# motor-driver.net
KiCad netlist of a schematic drawn in Altium Designer
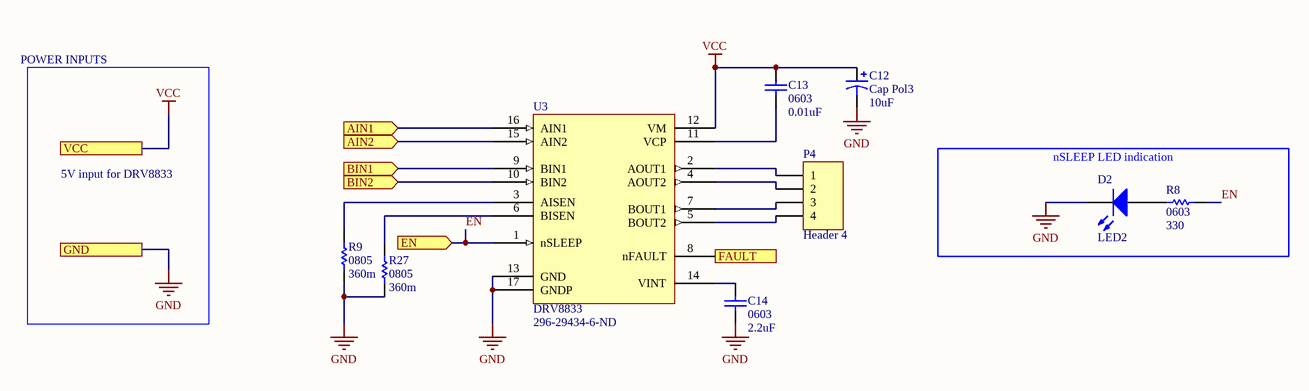
[diagram p0: motor-driver.SchDoc]

(export (version "E")
  (design (tool "Eeschema 10.0.6"))
  (components
    (comp (ref "C12")
      (value "Cap Pol3")
      (footprint "CAP DIA12.5mm")
      (description "Polarized Capacitor (through hole)")
      (fields (field (name "ALTIUM_VALUE") "10uF") (field (name "PUBLISHER") "Altium Limited"))
      (libsource (lib "Miscellaneous Devices") (part "Cap Pol3"))
    )
    (comp (ref "C13")
      (value "0603")
      (footprint "0603-RES")
      (description "Capacitor")
      (fields (field (name "ALTIUM_VALUE") "0.01uF") (field (name "PUBLISHER") "Altium Limited"))
      (libsource (lib "Miscellaneous Devices") (part "Cap"))
    )
    (comp (ref "C14")
      (value "0603")
      (footprint "0603-RES")
      (description "Capacitor")
      (fields (field (name "ALTIUM_VALUE") "2.2uF") (field (name "PUBLISHER") "Altium Limited"))
      (libsource (lib "Miscellaneous Devices") (part "Cap"))
    )
    (comp (ref "D2")
      (value "LED2")
      (footprint "0603-LED")
      (description "Typical RED, GREEN, YELLOW, AMBER GaAs LED")
      (fields (field (name "PUBLISHER") "Altium Limited"))
      (libsource (lib "Miscellaneous Devices") (part "LED2"))
    )
    (comp (ref "P4")
      (value "Header 4")
      (footprint "MOLEX_504050-0491")
      (description "Header, 4-Pin")
      (fields (field (name "PUBLISHER") "Altium Limited"))
      (libsource (lib "Miscellaneous Connectors") (part "Header 4"))
    )
    (comp (ref "R8")
      (value "0603")
      (footprint "0603-RES")
      (description "Resistor")
      (fields (field (name "ALTIUM_VALUE") "330") (field (name "PUBLISHER") "Altium Limited"))
      (libsource (lib "Miscellaneous Devices") (part "Res1"))
    )
    (comp (ref "R9")
      (value "0805")
      (footprint "6-0805_M")
      (description "Resistor")
      (fields (field (name "ALTIUM_VALUE") "360m") (field (name "PUBLISHER") "Altium Limited"))
      (libsource (lib "Miscellaneous Devices") (part "Res1"))
    )
    (comp (ref "R27")
      (value "0805")
      (footprint "6-0805_M")
      (description "Resistor")
      (fields (field (name "ALTIUM_VALUE") "360m") (field (name "PUBLISHER") "Altium Limited"))
      (libsource (lib "Miscellaneous Devices") (part "Res1"))
    )
    (comp (ref "U3")
      (value "DRV8833")
      (footprint "SOP65P640X120-17N")
      (fields (field (name "SUPPLIER PART NUMBER 1") "296-29434-6-ND"))
      (libsource (lib "PAY") (part "DRV8833"))
    )
  )
  (nets
    (net (code "1") (name "/AIN1") (class "Default")
      (node (ref "U3") (pin "16") (pinfunction "AIN1_16") (pintype "input"))
    )
    (net (code "2") (name "/AIN2") (class "Default")
      (node (ref "U3") (pin "15") (pinfunction "AIN2_15") (pintype "input"))
    )
    (net (code "3") (name "/BIN1") (class "Default")
      (node (ref "U3") (pin "9") (pinfunction "BIN1_9") (pintype "input"))
    )
    (net (code "4") (name "/BIN2") (class "Default")
      (node (ref "U3") (pin "10") (pinfunction "BIN2_10") (pintype "input"))
    )
    (net (code "5") (name "/EN") (class "Default")
      (node (ref "R8") (pin "2") (pinfunction "2_2") (pintype "passive"))
      (node (ref "U3") (pin "1") (pinfunction "nSLEEP_1") (pintype "input"))
    )
    (net (code "6") (name "/FAULT") (class "Default")
      (node (ref "U3") (pin "8") (pinfunction "nFAULT_8") (pintype "passive"))
    )
    (net (code "7") (name "GND") (class "Default")
      (node (ref "C12") (pin "2") (pinfunction "2_2") (pintype "passive"))
      (node (ref "C14") (pin "1") (pinfunction "1_1") (pintype "passive"))
      (node (ref "D2") (pin "2") (pinfunction "K_2") (pintype "passive"))
      (node (ref "R27") (pin "1") (pinfunction "1_1") (pintype "passive"))
      (node (ref "R9") (pin "1") (pinfunction "1_1") (pintype "passive"))
      (node (ref "U3") (pin "13") (pinfunction "GND_13") (pintype "power_in"))
      (node (ref "U3") (pin "17") (pinfunction "GNDP_17") (pintype "power_in"))
    )
    (net (code "8") (name "Net-(D2-A)") (class "Default")
      (node (ref "D2") (pin "1") (pinfunction "A_1") (pintype "passive"))
      (node (ref "R8") (pin "1") (pinfunction "1_1") (pintype "passive"))
    )
    (net (code "9") (name "Net-(U3-AISEN)") (class "Default")
      (node (ref "R9") (pin "2") (pinfunction "2_2") (pintype "passive"))
      (node (ref "U3") (pin "3") (pinfunction "AISEN_3") (pintype "passive"))
    )
    (net (code "10") (name "Net-(U3-AOUT1)") (class "Default")
      (node (ref "P4") (pin "1") (pinfunction "1_1") (pintype "passive"))
      (node (ref "U3") (pin "2") (pinfunction "AOUT1_2") (pintype "output"))
    )
    (net (code "11") (name "Net-(U3-AOUT2)") (class "Default")
      (node (ref "P4") (pin "2") (pinfunction "2_2") (pintype "passive"))
      (node (ref "U3") (pin "4") (pinfunction "AOUT2_4") (pintype "output"))
    )
    (net (code "12") (name "Net-(U3-BISEN)") (class "Default")
      (node (ref "R27") (pin "2") (pinfunction "2_2") (pintype "passive"))
      (node (ref "U3") (pin "6") (pinfunction "BISEN_6") (pintype "passive"))
    )
    (net (code "13") (name "Net-(U3-BOUT1)") (class "Default")
      (node (ref "P4") (pin "3") (pinfunction "3_3") (pintype "passive"))
      (node (ref "U3") (pin "7") (pinfunction "BOUT1_7") (pintype "output"))
    )
    (net (code "14") (name "Net-(U3-BOUT2)") (class "Default")
      (node (ref "P4") (pin "4") (pinfunction "4_4") (pintype "passive"))
      (node (ref "U3") (pin "5") (pinfunction "BOUT2_5") (pintype "output"))
    )
    (net (code "15") (name "Net-(U3-VCP)") (class "Default")
      (node (ref "C13") (pin "2") (pinfunction "2_2") (pintype "passive"))
      (node (ref "U3") (pin "11") (pinfunction "VCP_11") (pintype "power_in"))
    )
    (net (code "16") (name "Net-(U3-VINT)") (class "Default")
      (node (ref "C14") (pin "2") (pinfunction "2_2") (pintype "passive"))
      (node (ref "U3") (pin "14") (pinfunction "VINT_14") (pintype "power_in"))
    )
    (net (code "17") (name "VCC") (class "Default")
      (node (ref "C12") (pin "1") (pinfunction "1_1") (pintype "passive"))
      (node (ref "C13") (pin "1") (pinfunction "1_1") (pintype "passive"))
      (node (ref "U3") (pin "12") (pinfunction "VM_12") (pintype "power_in"))
    )
  )
)
